# TEST_BED_BATT_DISP.net
KiCad netlist of a schematic drawn in EAGLE
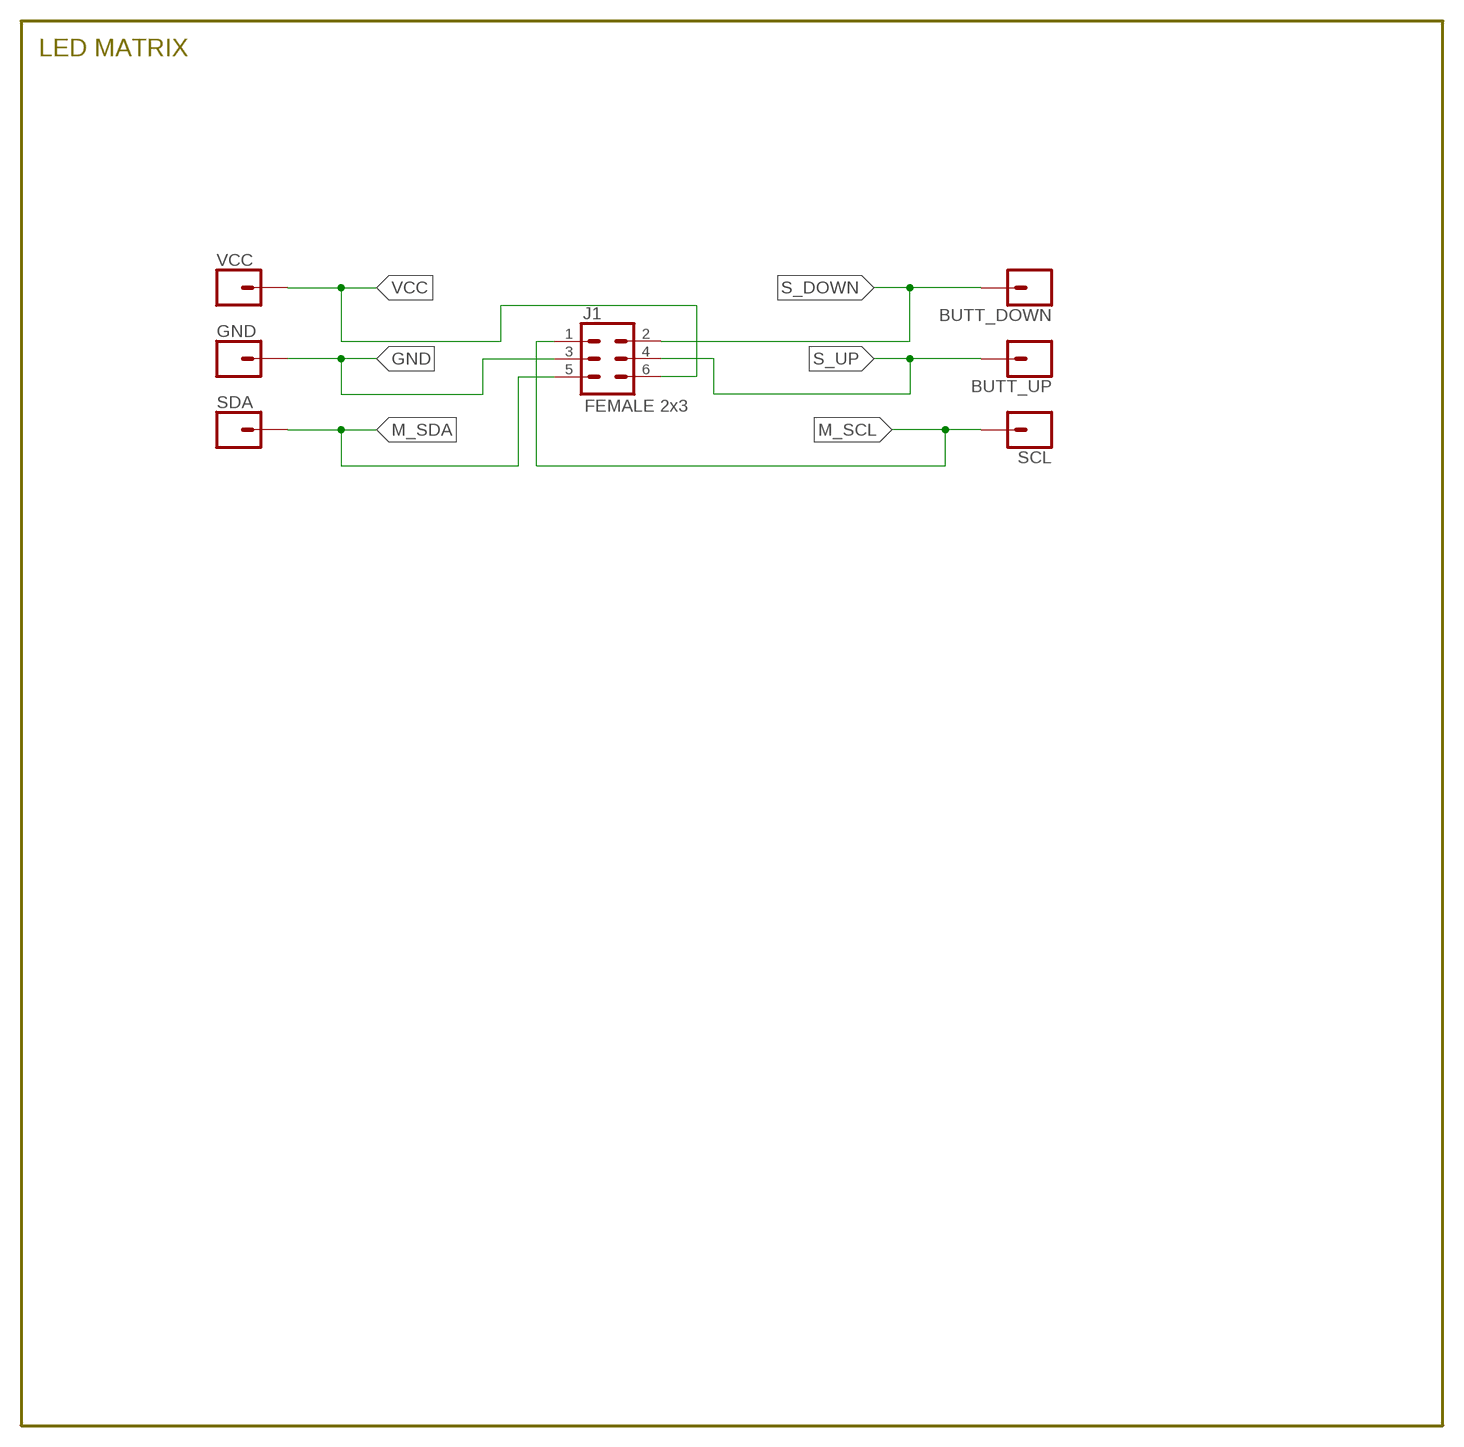
[diagram p0: schematic, sheet 1]

(export (version "E")
  (design (tool "Eeschema 10.0.6"))
  (components
    (comp (ref "BUTT_DOWN")
      (value "CONN_01POGOPIN_HOLE_LARGE")
      (footprint "eagle-import:1X01_POGOPIN_HOLE_0.061_DIA")
      (libsource (lib "eagle-import") (part "CONN_01POGOPIN_HOLE_LARGE"))
    )
    (comp (ref "BUTT_UP")
      (value "CONN_01POGOPIN_HOLE_LARGE")
      (footprint "eagle-import:1X01_POGOPIN_HOLE_0.061_DIA")
      (libsource (lib "eagle-import") (part "CONN_01POGOPIN_HOLE_LARGE"))
    )
    (comp (ref "GND")
      (value "CONN_01POGOPIN_HOLE_LARGE")
      (footprint "eagle-import:1X01_POGOPIN_HOLE_0.061_DIA")
      (libsource (lib "eagle-import") (part "CONN_01POGOPIN_HOLE_LARGE"))
    )
    (comp (ref "J1")
      (value "FEMALE 2x3")
      (footprint "eagle-import:2X3")
      (libsource (lib "eagle-import") (part "CONN_03X2FEMALE"))
    )
    (comp (ref "SCL")
      (value "CONN_01POGOPIN_HOLE_LARGE")
      (footprint "eagle-import:1X01_POGOPIN_HOLE_0.061_DIA")
      (libsource (lib "eagle-import") (part "CONN_01POGOPIN_HOLE_LARGE"))
    )
    (comp (ref "SDA")
      (value "CONN_01POGOPIN_HOLE_LARGE")
      (footprint "eagle-import:1X01_POGOPIN_HOLE_0.061_DIA")
      (libsource (lib "eagle-import") (part "CONN_01POGOPIN_HOLE_LARGE"))
    )
    (comp (ref "VCC")
      (value "CONN_01POGOPIN_HOLE_LARGE")
      (footprint "eagle-import:1X01_POGOPIN_HOLE_0.061_DIA")
      (libsource (lib "eagle-import") (part "CONN_01POGOPIN_HOLE_LARGE"))
    )
  )
  (nets
    (net (code "1") (name "GND") (class "Default")
      (node (ref "GND") (pin "2") (pinfunction "1_2") (pintype "passive"))
      (node (ref "J1") (pin "3") (pinfunction "3_3") (pintype "bidirectional"))
    )
    (net (code "2") (name "M_SCL") (class "Default")
      (node (ref "J1") (pin "1") (pinfunction "1_1") (pintype "bidirectional"))
      (node (ref "SCL") (pin "2") (pinfunction "1_2") (pintype "passive"))
    )
    (net (code "3") (name "M_SDA") (class "Default")
      (node (ref "J1") (pin "5") (pinfunction "5_5") (pintype "bidirectional"))
      (node (ref "SDA") (pin "2") (pinfunction "1_2") (pintype "passive"))
    )
    (net (code "4") (name "S_DOWN") (class "Default")
      (node (ref "BUTT_DOWN") (pin "2") (pinfunction "1_2") (pintype "passive"))
      (node (ref "J1") (pin "2") (pinfunction "2_2") (pintype "bidirectional"))
    )
    (net (code "5") (name "S_UP") (class "Default")
      (node (ref "BUTT_UP") (pin "2") (pinfunction "1_2") (pintype "passive"))
      (node (ref "J1") (pin "4") (pinfunction "4_4") (pintype "bidirectional"))
    )
    (net (code "6") (name "VCC") (class "Default")
      (node (ref "J1") (pin "6") (pinfunction "6_6") (pintype "bidirectional"))
      (node (ref "VCC") (pin "2") (pinfunction "1_2") (pintype "passive"))
    )
  )
)
